# mrShark_Programmer.net
KiCad netlist of a schematic drawn in EAGLE
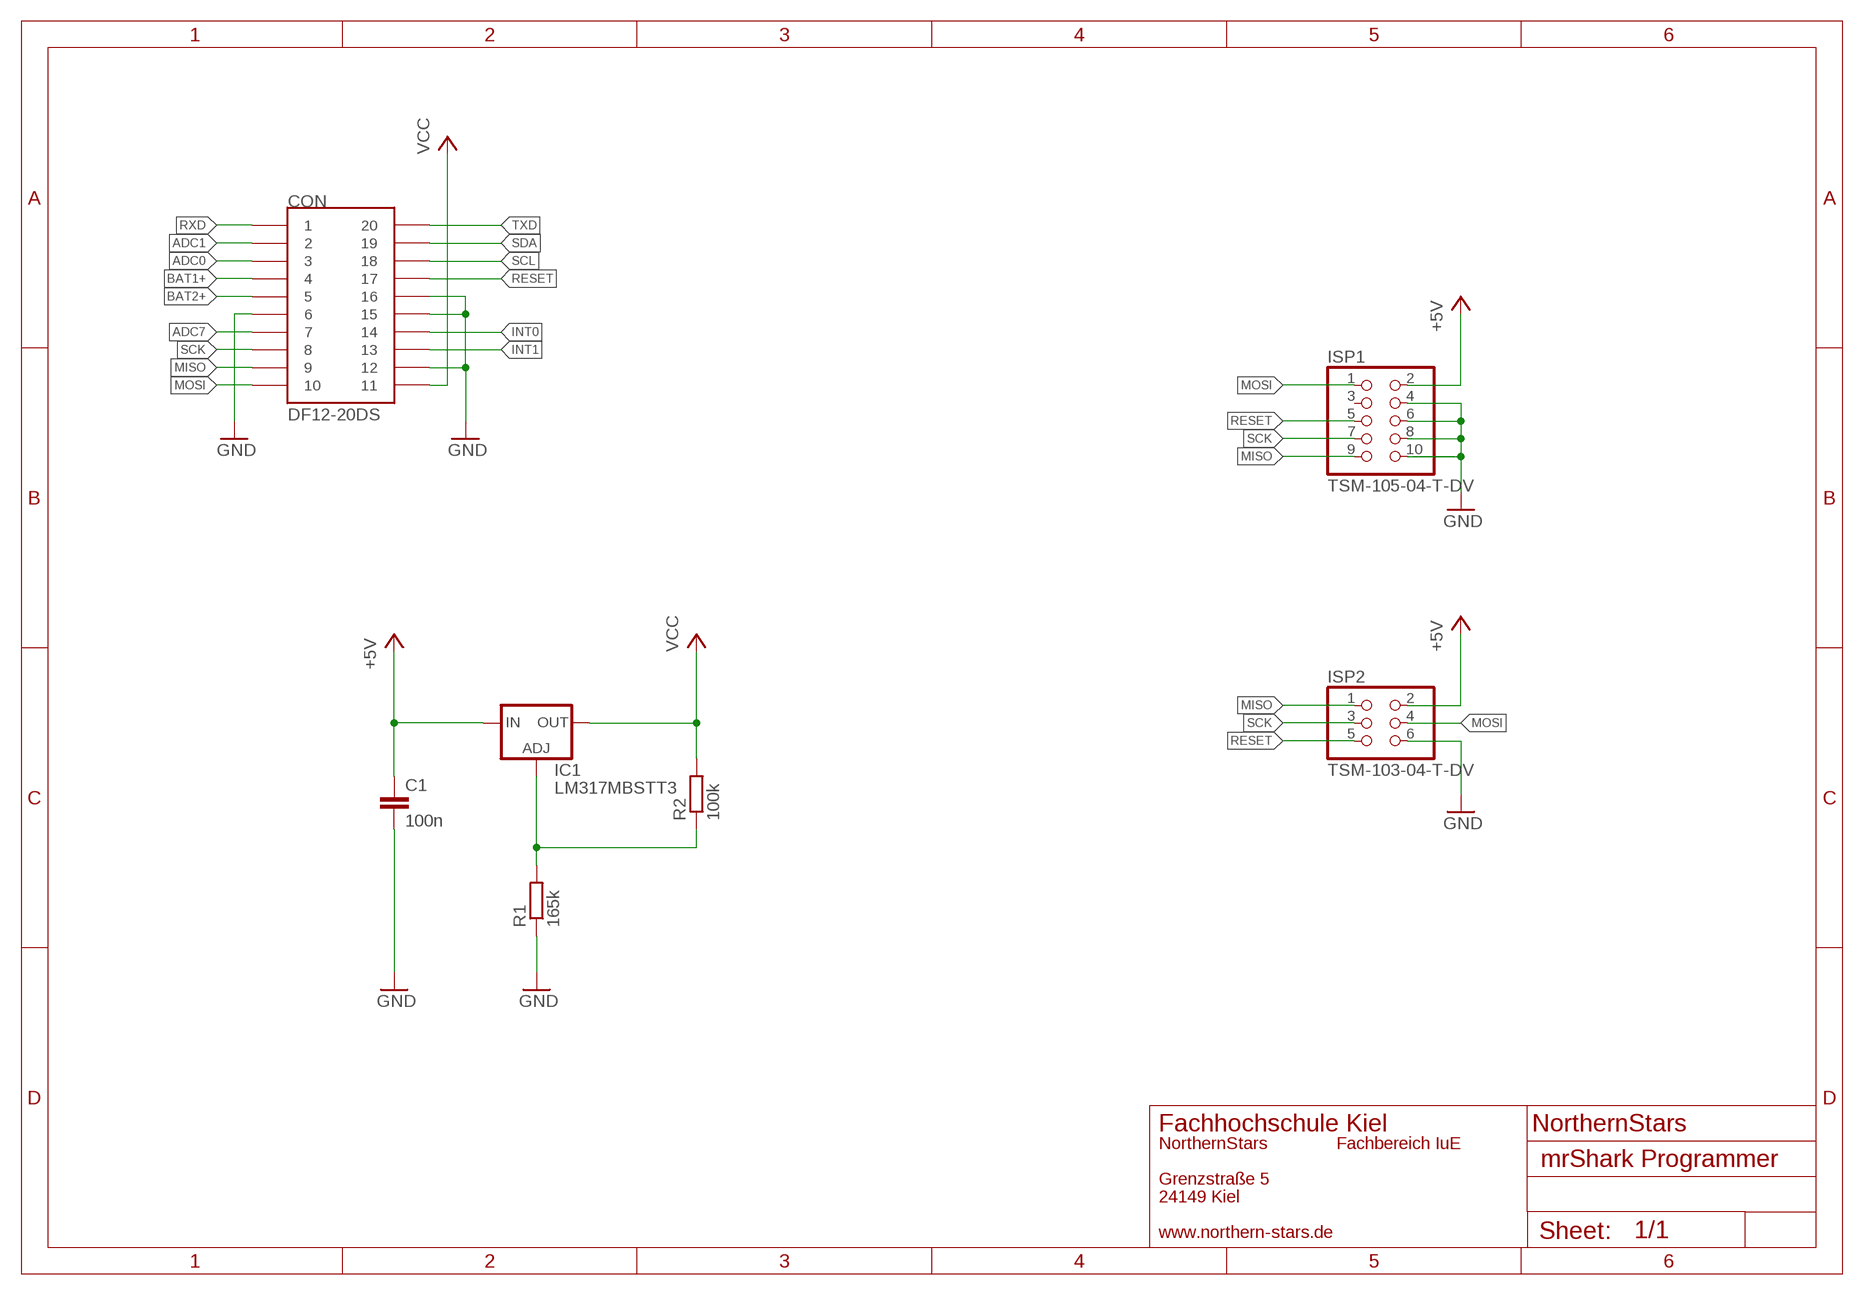
[diagram p0: schematic, sheet 1]

(export (version "E")
  (design (tool "Eeschema 10.0.6"))
  (components
    (comp (ref "C1")
      (value "100n")
      (footprint "eagle-import:C0201")
      (libsource (lib "eagle-import") (part "C-EUC0201"))
    )
    (comp (ref "CON")
      (value "DF12-20DS")
      (footprint "eagle-import:DF12-20DS")
      (libsource (lib "eagle-import") (part "DF12-20DS"))
    )
    (comp (ref "IC1")
      (value "LM317MBSTT3")
      (footprint "eagle-import:SOT223")
      (libsource (lib "eagle-import") (part "LM317?MBSTT3"))
    )
    (comp (ref "ISP1")
      (value "TSM-105-04-T-DV")
      (footprint "eagle-import:2X05SMD")
      (libsource (lib "eagle-import") (part "PINHD-2X05_2.54-SMD"))
    )
    (comp (ref "ISP2")
      (value "TSM-103-04-T-DV")
      (footprint "eagle-import:2X03SMD")
      (libsource (lib "eagle-import") (part "PINHD-2X03_2.54-SMD"))
    )
    (comp (ref "R1")
      (value "165k")
      (footprint "eagle-import:R0201")
      (libsource (lib "eagle-import") (part "R-EU_R0201"))
    )
    (comp (ref "R2")
      (value "100k")
      (footprint "eagle-import:R0201")
      (libsource (lib "eagle-import") (part "R-EU_R0201"))
    )
  )
  (nets
    (net (code "1") (name "+5V") (class "Default")
      (node (ref "C1") (pin "1") (pinfunction "1_1") (pintype "passive"))
      (node (ref "IC1") (pin "3") (pinfunction "IN_3") (pintype "input"))
      (node (ref "ISP1") (pin "2") (pinfunction "2_2") (pintype "passive"))
      (node (ref "ISP2") (pin "2") (pinfunction "2_2") (pintype "passive"))
    )
    (net (code "2") (name "ADC0") (class "Default")
      (node (ref "CON") (pin "3") (pinfunction "3_3") (pintype "bidirectional"))
    )
    (net (code "3") (name "ADC1") (class "Default")
      (node (ref "CON") (pin "2") (pinfunction "2_2") (pintype "bidirectional"))
    )
    (net (code "4") (name "ADC7") (class "Default")
      (node (ref "CON") (pin "7") (pinfunction "7_7") (pintype "bidirectional"))
    )
    (net (code "5") (name "BAT1+") (class "Default")
      (node (ref "CON") (pin "4") (pinfunction "4_4") (pintype "bidirectional"))
    )
    (net (code "6") (name "BAT2+") (class "Default")
      (node (ref "CON") (pin "5") (pinfunction "5_5") (pintype "bidirectional"))
    )
    (net (code "7") (name "GND") (class "Default")
      (node (ref "C1") (pin "2") (pinfunction "2_2") (pintype "passive"))
      (node (ref "CON") (pin "12") (pinfunction "12_12") (pintype "bidirectional"))
      (node (ref "CON") (pin "15") (pinfunction "15_15") (pintype "bidirectional"))
      (node (ref "CON") (pin "16") (pinfunction "16_16") (pintype "bidirectional"))
      (node (ref "CON") (pin "6") (pinfunction "6_6") (pintype "bidirectional"))
      (node (ref "ISP1") (pin "10") (pinfunction "10_10") (pintype "passive"))
      (node (ref "ISP1") (pin "4") (pinfunction "4_4") (pintype "passive"))
      (node (ref "ISP1") (pin "6") (pinfunction "6_6") (pintype "passive"))
      (node (ref "ISP1") (pin "8") (pinfunction "8_8") (pintype "passive"))
      (node (ref "ISP2") (pin "6") (pinfunction "6_6") (pintype "passive"))
      (node (ref "R1") (pin "1") (pinfunction "1_1") (pintype "passive"))
    )
    (net (code "8") (name "INT0") (class "Default")
      (node (ref "CON") (pin "14") (pinfunction "14_14") (pintype "bidirectional"))
    )
    (net (code "9") (name "INT1") (class "Default")
      (node (ref "CON") (pin "13") (pinfunction "13_13") (pintype "bidirectional"))
    )
    (net (code "10") (name "MISO") (class "Default")
      (node (ref "CON") (pin "9") (pinfunction "9_9") (pintype "bidirectional"))
      (node (ref "ISP1") (pin "9") (pinfunction "9_9") (pintype "passive"))
      (node (ref "ISP2") (pin "1") (pinfunction "1_1") (pintype "passive"))
    )
    (net (code "11") (name "MOSI") (class "Default")
      (node (ref "CON") (pin "10") (pinfunction "10_10") (pintype "bidirectional"))
      (node (ref "ISP1") (pin "1") (pinfunction "1_1") (pintype "passive"))
      (node (ref "ISP2") (pin "4") (pinfunction "4_4") (pintype "passive"))
    )
    (net (code "12") (name "Net-(IC1-ADJ)") (class "Default")
      (node (ref "IC1") (pin "1") (pinfunction "ADJ_1") (pintype "input"))
      (node (ref "R1") (pin "2") (pinfunction "2_2") (pintype "passive"))
      (node (ref "R2") (pin "1") (pinfunction "1_1") (pintype "passive"))
    )
    (net (code "13") (name "RESET") (class "Default")
      (node (ref "CON") (pin "17") (pinfunction "17_17") (pintype "bidirectional"))
      (node (ref "ISP1") (pin "5") (pinfunction "5_5") (pintype "passive"))
      (node (ref "ISP2") (pin "5") (pinfunction "5_5") (pintype "passive"))
    )
    (net (code "14") (name "RXD") (class "Default")
      (node (ref "CON") (pin "1") (pinfunction "1_1") (pintype "bidirectional"))
    )
    (net (code "15") (name "SCK") (class "Default")
      (node (ref "CON") (pin "8") (pinfunction "8_8") (pintype "bidirectional"))
      (node (ref "ISP1") (pin "7") (pinfunction "7_7") (pintype "passive"))
      (node (ref "ISP2") (pin "3") (pinfunction "3_3") (pintype "passive"))
    )
    (net (code "16") (name "SCL") (class "Default")
      (node (ref "CON") (pin "18") (pinfunction "18_18") (pintype "bidirectional"))
    )
    (net (code "17") (name "SDA") (class "Default")
      (node (ref "CON") (pin "19") (pinfunction "19_19") (pintype "bidirectional"))
    )
    (net (code "18") (name "TXD") (class "Default")
      (node (ref "CON") (pin "20") (pinfunction "20_20") (pintype "bidirectional"))
    )
    (net (code "19") (name "VCC") (class "Default")
      (node (ref "CON") (pin "11") (pinfunction "11_11") (pintype "bidirectional"))
      (node (ref "IC1") (pin "4") (pinfunction "OUT_4") (pintype "passive"))
      (node (ref "R2") (pin "2") (pinfunction "2_2") (pintype "passive"))
    )
    (net (code "20") (name "unconnected-(ISP1-Pad3)") (class "Default")
      (node (ref "ISP1") (pin "3") (pinfunction "3_3") (pintype "passive"))
    )
  )
)
